# Fan_Driver.net
KiCad netlist of a schematic drawn in Altium Designer
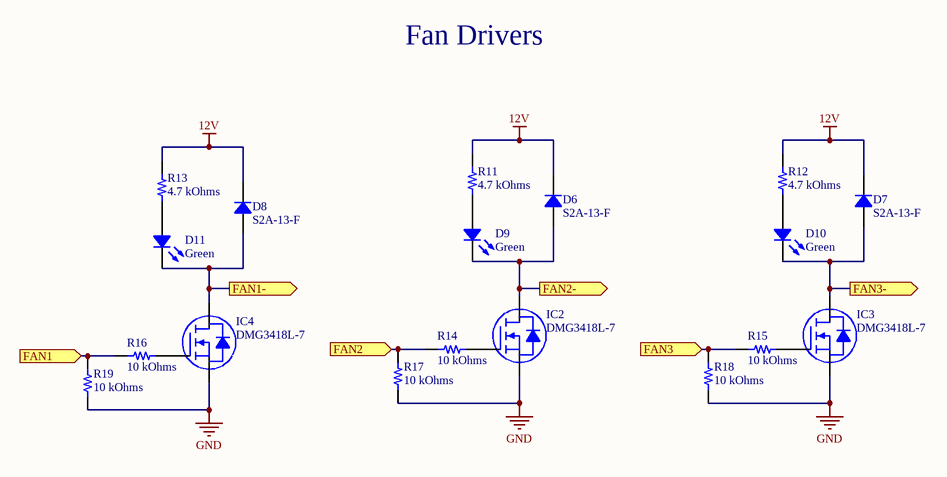
[diagram p0: Fan Driver.SchDoc]

(export (version "E")
  (design (tool "Eeschema 10.0.6"))
  (components
    (comp (ref "D6")
      (value "S2A-13-F")
      (footprint "DO214AA SMB")
      (description "DIODE GEN PURP 50V 1.5A SMB")
      (fields (field (name "MANUFACTURER") "Diodes Incorporated"))
      (libsource (lib "Celestial Altium Library - altium_library") (part "Diode"))
    )
    (comp (ref "D7")
      (value "S2A-13-F")
      (footprint "DO214AA SMB")
      (description "DIODE GEN PURP 50V 1.5A SMB")
      (fields (field (name "MANUFACTURER") "Diodes Incorporated"))
      (libsource (lib "Celestial Altium Library - altium_library") (part "Diode"))
    )
    (comp (ref "D8")
      (value "S2A-13-F")
      (footprint "DO214AA SMB")
      (description "DIODE GEN PURP 50V 1.5A SMB")
      (fields (field (name "MANUFACTURER") "Diodes Incorporated"))
      (libsource (lib "Celestial Altium Library - altium_library") (part "Diode"))
    )
    (comp (ref "D9")
      (value "Green")
      (footprint "LED 0603_1608 GREEN")
      (description "LED GREEN CLEAR 2SMD")
      (fields (field (name "PART NUMBER") "XZVGT53W-6") (field (name "MANUFACTURER") "SunLED"))
      (libsource (lib "Celestial Altium Library - altium_library") (part "LED"))
    )
    (comp (ref "D10")
      (value "Green")
      (footprint "LED 0603_1608 GREEN")
      (description "LED GREEN CLEAR 2SMD")
      (fields (field (name "PART NUMBER") "XZVGT53W-6") (field (name "MANUFACTURER") "SunLED"))
      (libsource (lib "Celestial Altium Library - altium_library") (part "LED"))
    )
    (comp (ref "D11")
      (value "Green")
      (footprint "LED 0603_1608 GREEN")
      (description "LED GREEN CLEAR 2SMD")
      (fields (field (name "PART NUMBER") "XZVGT53W-6") (field (name "MANUFACTURER") "SunLED"))
      (libsource (lib "Celestial Altium Library - altium_library") (part "LED"))
    )
    (comp (ref "IC2")
      (value "DMG3418L-7")
      (footprint "DIODES SOT-23-3")
      (description "MOSFET N-CH 30V 4A SOT23")
      (fields (field (name "MANUFACTURER") "Diodes Incorporated"))
      (libsource (lib "Celestial Altium Library - altium_library") (part "DIODES INC MOSFET N-CH SOT-23-3"))
    )
    (comp (ref "IC3")
      (value "DMG3418L-7")
      (footprint "DIODES SOT-23-3")
      (description "MOSFET N-CH 30V 4A SOT23")
      (fields (field (name "MANUFACTURER") "Diodes Incorporated"))
      (libsource (lib "Celestial Altium Library - altium_library") (part "DIODES INC MOSFET N-CH SOT-23-3"))
    )
    (comp (ref "IC4")
      (value "DMG3418L-7")
      (footprint "DIODES SOT-23-3")
      (description "MOSFET N-CH 30V 4A SOT23")
      (fields (field (name "MANUFACTURER") "Diodes Incorporated"))
      (libsource (lib "Celestial Altium Library - altium_library") (part "DIODES INC MOSFET N-CH SOT-23-3"))
    )
    (comp (ref "R11")
      (value "4.7 kOhms")
      (footprint "RES 0603_1608")
      (description "RES SMD 4.7K OHM 1% 1/10W 0603")
      (fields
        (field (name "PART NUMBER") "ERJ-3EKF4701V")
        (field (name "MANUFACTURER") "Panasonic Electronic Components")
      )
      (libsource (lib "Celestial Altium Library - altium_library") (part "Resistor"))
    )
    (comp (ref "R12")
      (value "4.7 kOhms")
      (footprint "RES 0603_1608")
      (description "RES SMD 4.7K OHM 1% 1/10W 0603")
      (fields
        (field (name "PART NUMBER") "ERJ-3EKF4701V")
        (field (name "MANUFACTURER") "Panasonic Electronic Components")
      )
      (libsource (lib "Celestial Altium Library - altium_library") (part "Resistor"))
    )
    (comp (ref "R13")
      (value "4.7 kOhms")
      (footprint "RES 0603_1608")
      (description "RES SMD 4.7K OHM 1% 1/10W 0603")
      (fields
        (field (name "PART NUMBER") "ERJ-3EKF4701V")
        (field (name "MANUFACTURER") "Panasonic Electronic Components")
      )
      (libsource (lib "Celestial Altium Library - altium_library") (part "Resistor"))
    )
    (comp (ref "R14")
      (value "10 kOhms")
      (footprint "RES 0603_1608")
      (description "RES SMD 10K OHM 1% 1/10W 0603")
      (fields (field (name "PART NUMBER") "RT0603FRE0710KL") (field (name "MANUFACTURER") "Yageo"))
      (libsource (lib "Celestial Altium Library - altium_library") (part "Resistor"))
    )
    (comp (ref "R15")
      (value "10 kOhms")
      (footprint "RES 0603_1608")
      (description "RES SMD 10K OHM 1% 1/10W 0603")
      (fields (field (name "PART NUMBER") "RT0603FRE0710KL") (field (name "MANUFACTURER") "Yageo"))
      (libsource (lib "Celestial Altium Library - altium_library") (part "Resistor"))
    )
    (comp (ref "R16")
      (value "10 kOhms")
      (footprint "RES 0603_1608")
      (description "RES SMD 10K OHM 1% 1/10W 0603")
      (fields (field (name "PART NUMBER") "RT0603FRE0710KL") (field (name "MANUFACTURER") "Yageo"))
      (libsource (lib "Celestial Altium Library - altium_library") (part "Resistor"))
    )
    (comp (ref "R17")
      (value "10 kOhms")
      (footprint "RES 0603_1608")
      (description "RES SMD 10K OHM 1% 1/10W 0603")
      (fields (field (name "PART NUMBER") "RT0603FRE0710KL") (field (name "MANUFACTURER") "Yageo"))
      (libsource (lib "Celestial Altium Library - altium_library") (part "Resistor"))
    )
    (comp (ref "R18")
      (value "10 kOhms")
      (footprint "RES 0603_1608")
      (description "RES SMD 10K OHM 1% 1/10W 0603")
      (fields (field (name "PART NUMBER") "RT0603FRE0710KL") (field (name "MANUFACTURER") "Yageo"))
      (libsource (lib "Celestial Altium Library - altium_library") (part "Resistor"))
    )
    (comp (ref "R19")
      (value "10 kOhms")
      (footprint "RES 0603_1608")
      (description "RES SMD 10K OHM 1% 1/10W 0603")
      (fields (field (name "PART NUMBER") "RT0603FRE0710KL") (field (name "MANUFACTURER") "Yageo"))
      (libsource (lib "Celestial Altium Library - altium_library") (part "Resistor"))
    )
  )
  (nets
    (net (code "1") (name "/FAN1") (class "Default")
      (node (ref "R16") (pin "2") (pinfunction "2_2") (pintype "passive"))
      (node (ref "R19") (pin "2") (pinfunction "2_2") (pintype "passive"))
    )
    (net (code "2") (name "/FAN1-") (class "Default")
      (node (ref "D11") (pin "2") (pinfunction "2_2") (pintype "passive"))
      (node (ref "D8") (pin "1") (pinfunction "1_1") (pintype "passive"))
      (node (ref "IC4") (pin "3") (pinfunction "D_3") (pintype "passive"))
    )
    (net (code "3") (name "/FAN2") (class "Default")
      (node (ref "R14") (pin "2") (pinfunction "2_2") (pintype "passive"))
      (node (ref "R17") (pin "2") (pinfunction "2_2") (pintype "passive"))
    )
    (net (code "4") (name "/FAN2-") (class "Default")
      (node (ref "D6") (pin "1") (pinfunction "1_1") (pintype "passive"))
      (node (ref "D9") (pin "2") (pinfunction "2_2") (pintype "passive"))
      (node (ref "IC2") (pin "3") (pinfunction "D_3") (pintype "passive"))
    )
    (net (code "5") (name "/FAN3") (class "Default")
      (node (ref "R15") (pin "2") (pinfunction "2_2") (pintype "passive"))
      (node (ref "R18") (pin "2") (pinfunction "2_2") (pintype "passive"))
    )
    (net (code "6") (name "/FAN3-") (class "Default")
      (node (ref "D10") (pin "2") (pinfunction "2_2") (pintype "passive"))
      (node (ref "D7") (pin "1") (pinfunction "1_1") (pintype "passive"))
      (node (ref "IC3") (pin "3") (pinfunction "D_3") (pintype "passive"))
    )
    (net (code "7") (name "12V") (class "Default")
      (node (ref "D6") (pin "2") (pinfunction "2_2") (pintype "passive"))
      (node (ref "D7") (pin "2") (pinfunction "2_2") (pintype "passive"))
      (node (ref "D8") (pin "2") (pinfunction "2_2") (pintype "passive"))
      (node (ref "R11") (pin "2") (pinfunction "2_2") (pintype "passive"))
      (node (ref "R12") (pin "2") (pinfunction "2_2") (pintype "passive"))
      (node (ref "R13") (pin "2") (pinfunction "2_2") (pintype "passive"))
    )
    (net (code "8") (name "GND") (class "Default")
      (node (ref "IC2") (pin "2") (pinfunction "S_2") (pintype "passive"))
      (node (ref "IC3") (pin "2") (pinfunction "S_2") (pintype "passive"))
      (node (ref "IC4") (pin "2") (pinfunction "S_2") (pintype "passive"))
      (node (ref "R17") (pin "1") (pinfunction "1_1") (pintype "passive"))
      (node (ref "R18") (pin "1") (pinfunction "1_1") (pintype "passive"))
      (node (ref "R19") (pin "1") (pinfunction "1_1") (pintype "passive"))
    )
    (net (code "9") (name "Net-(D9-Pad1)") (class "Default")
      (node (ref "D9") (pin "1") (pinfunction "1_1") (pintype "passive"))
      (node (ref "R11") (pin "1") (pinfunction "1_1") (pintype "passive"))
    )
    (net (code "10") (name "Net-(D10-Pad1)") (class "Default")
      (node (ref "D10") (pin "1") (pinfunction "1_1") (pintype "passive"))
      (node (ref "R12") (pin "1") (pinfunction "1_1") (pintype "passive"))
    )
    (net (code "11") (name "Net-(D11-Pad1)") (class "Default")
      (node (ref "D11") (pin "1") (pinfunction "1_1") (pintype "passive"))
      (node (ref "R13") (pin "1") (pinfunction "1_1") (pintype "passive"))
    )
    (net (code "12") (name "Net-(IC2-G)") (class "Default")
      (node (ref "IC2") (pin "1") (pinfunction "G_1") (pintype "passive"))
      (node (ref "R14") (pin "1") (pinfunction "1_1") (pintype "passive"))
    )
    (net (code "13") (name "Net-(IC3-G)") (class "Default")
      (node (ref "IC3") (pin "1") (pinfunction "G_1") (pintype "passive"))
      (node (ref "R15") (pin "1") (pinfunction "1_1") (pintype "passive"))
    )
    (net (code "14") (name "Net-(IC4-G)") (class "Default")
      (node (ref "IC4") (pin "1") (pinfunction "G_1") (pintype "passive"))
      (node (ref "R16") (pin "1") (pinfunction "1_1") (pintype "passive"))
    )
  )
)
